# maclight-v1.net
KiCad netlist of a schematic drawn in EAGLE
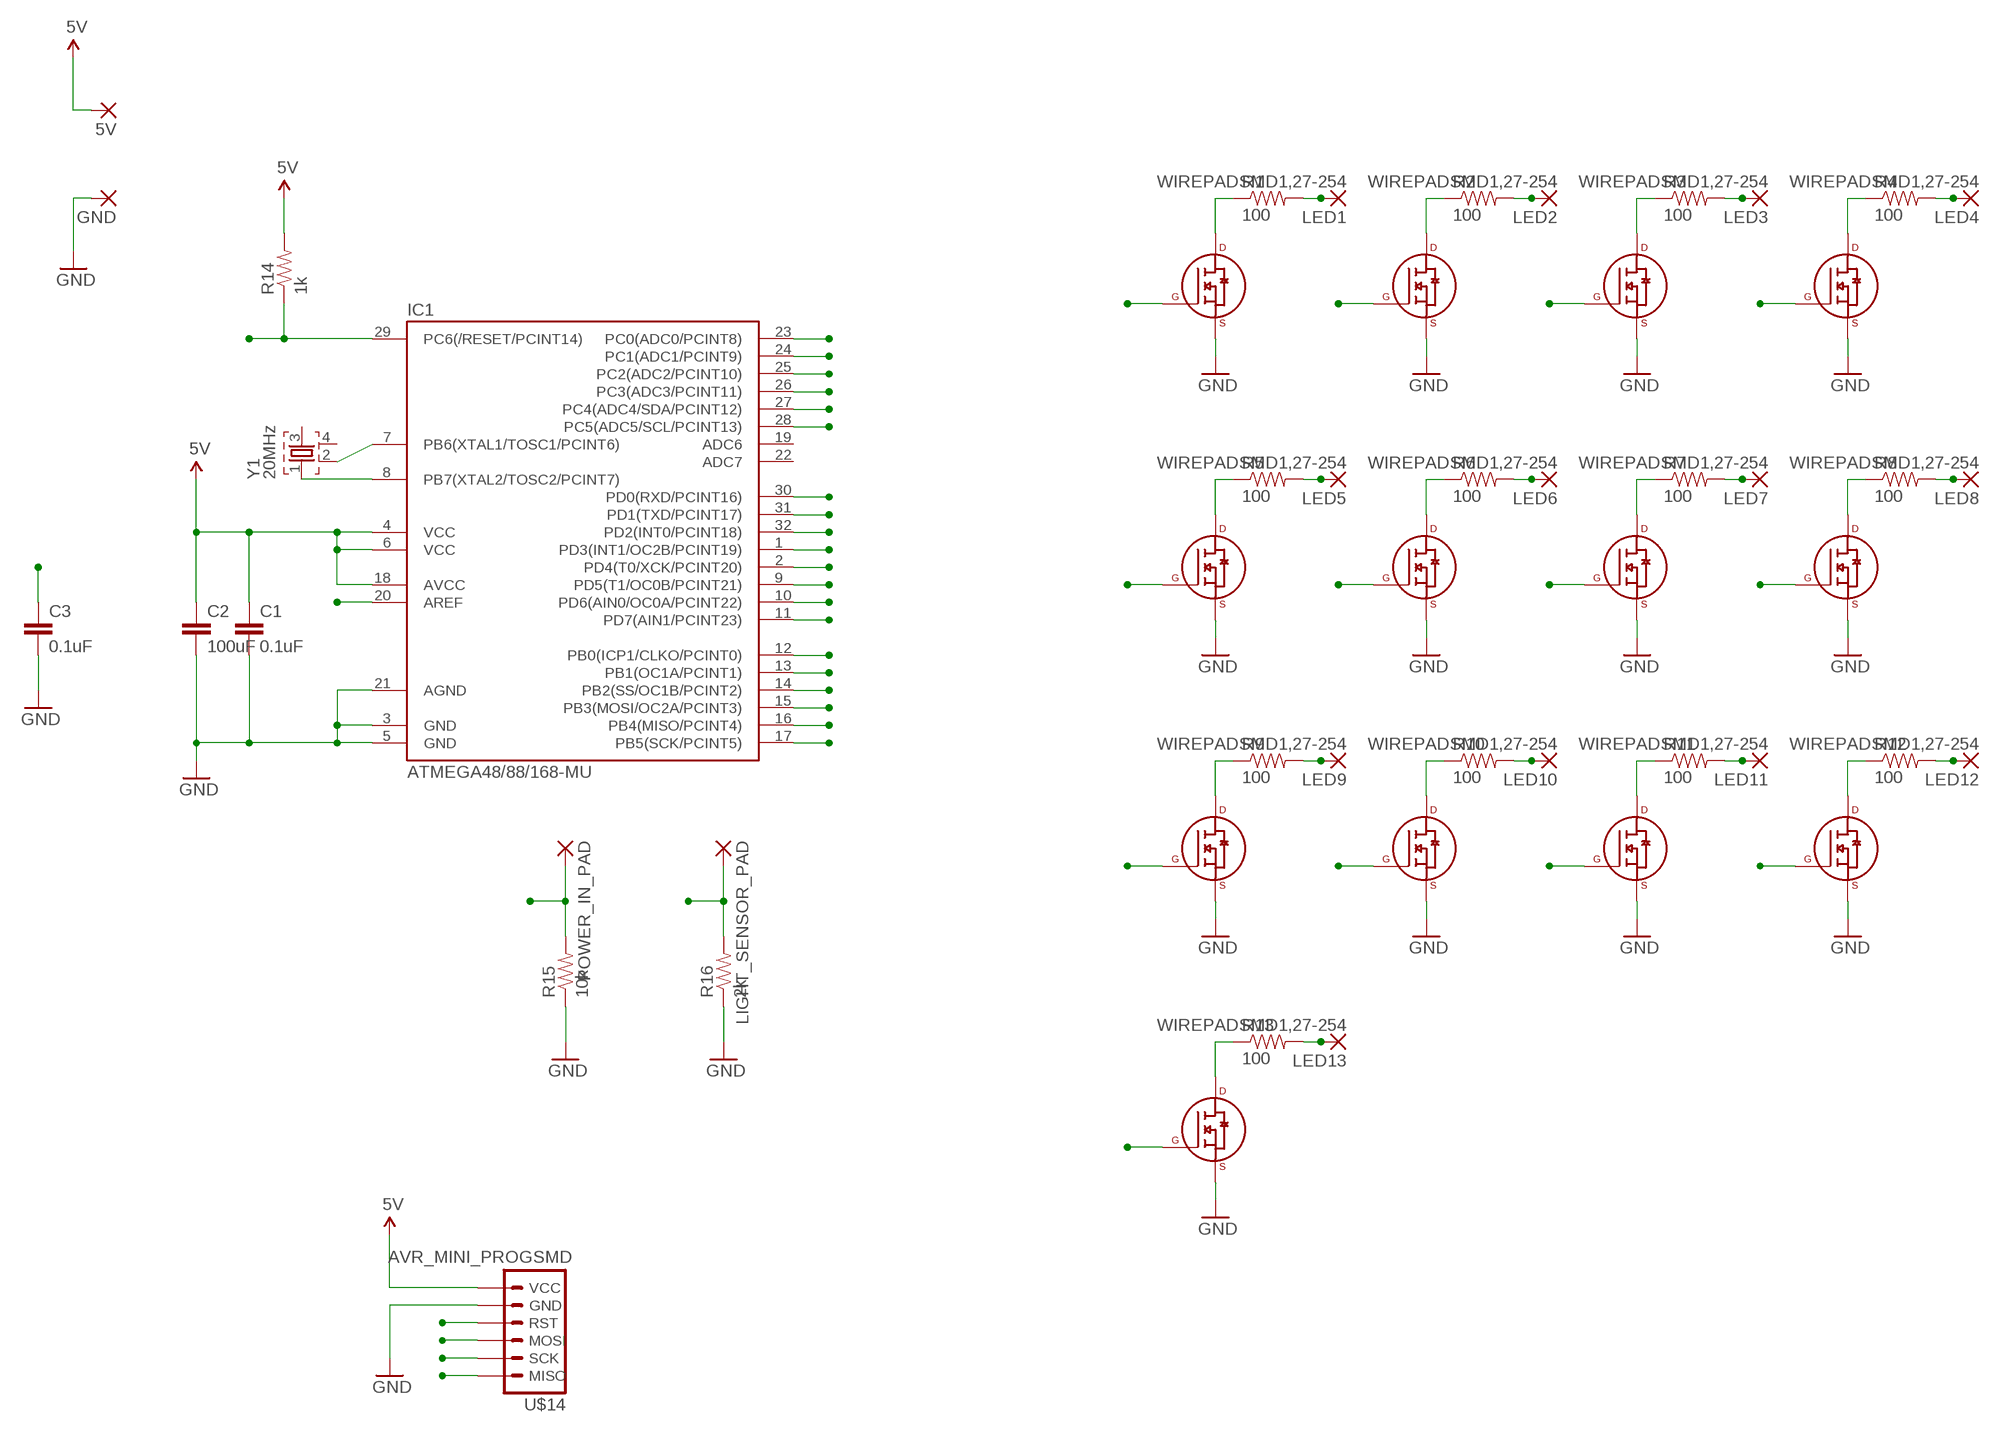
[diagram p0: schematic, sheet 1]

(export (version "E")
  (design (tool "Eeschema 10.0.6"))
  (components
    (comp (ref "5V")
      (value "WIREPADSMD5-1,8")
      (footprint "eagle-import:5-1,8")
      (libsource (lib "eagle-import") (part "WIREPADSMD5-1,8"))
    )
    (comp (ref "C1")
      (value "0.1uF")
      (footprint "eagle-import:0805")
      (libsource (lib "eagle-import") (part "CAP0805"))
    )
    (comp (ref "C2")
      (value "100uF")
      (footprint "eagle-import:1206")
      (libsource (lib "eagle-import") (part "CAP1206"))
    )
    (comp (ref "C3")
      (value "0.1uF")
      (footprint "eagle-import:0805")
      (libsource (lib "eagle-import") (part "CAP0805"))
    )
    (comp (ref "GND")
      (value "WIREPADSMD5-1,8")
      (footprint "eagle-import:5-1,8")
      (libsource (lib "eagle-import") (part "WIREPADSMD5-1,8"))
    )
    (comp (ref "IC1")
      (value "ATMEGA48/88/168-MU")
      (footprint "eagle-import:MLF32")
      (libsource (lib "eagle-import") (part "ATMEGA48/88/168-MU"))
    )
    (comp (ref "LED1")
      (value "WIREPADSMD1,27-254")
      (footprint "eagle-import:SMD1,27-2,54")
      (libsource (lib "eagle-import") (part "WIREPADSMD1,27-254"))
    )
    (comp (ref "LED2")
      (value "WIREPADSMD1,27-254")
      (footprint "eagle-import:SMD1,27-2,54")
      (libsource (lib "eagle-import") (part "WIREPADSMD1,27-254"))
    )
    (comp (ref "LED3")
      (value "WIREPADSMD1,27-254")
      (footprint "eagle-import:SMD1,27-2,54")
      (libsource (lib "eagle-import") (part "WIREPADSMD1,27-254"))
    )
    (comp (ref "LED4")
      (value "WIREPADSMD1,27-254")
      (footprint "eagle-import:SMD1,27-2,54")
      (libsource (lib "eagle-import") (part "WIREPADSMD1,27-254"))
    )
    (comp (ref "LED5")
      (value "WIREPADSMD1,27-254")
      (footprint "eagle-import:SMD1,27-2,54")
      (libsource (lib "eagle-import") (part "WIREPADSMD1,27-254"))
    )
    (comp (ref "LED6")
      (value "WIREPADSMD1,27-254")
      (footprint "eagle-import:SMD1,27-2,54")
      (libsource (lib "eagle-import") (part "WIREPADSMD1,27-254"))
    )
    (comp (ref "LED7")
      (value "WIREPADSMD1,27-254")
      (footprint "eagle-import:SMD1,27-2,54")
      (libsource (lib "eagle-import") (part "WIREPADSMD1,27-254"))
    )
    (comp (ref "LED8")
      (value "WIREPADSMD1,27-254")
      (footprint "eagle-import:SMD1,27-2,54")
      (libsource (lib "eagle-import") (part "WIREPADSMD1,27-254"))
    )
    (comp (ref "LED9")
      (value "WIREPADSMD1,27-254")
      (footprint "eagle-import:SMD1,27-2,54")
      (libsource (lib "eagle-import") (part "WIREPADSMD1,27-254"))
    )
    (comp (ref "LED10")
      (value "WIREPADSMD1,27-254")
      (footprint "eagle-import:SMD1,27-2,54")
      (libsource (lib "eagle-import") (part "WIREPADSMD1,27-254"))
    )
    (comp (ref "LED11")
      (value "WIREPADSMD1,27-254")
      (footprint "eagle-import:SMD1,27-2,54")
      (libsource (lib "eagle-import") (part "WIREPADSMD1,27-254"))
    )
    (comp (ref "LED12")
      (value "WIREPADSMD1,27-254")
      (footprint "eagle-import:SMD1,27-2,54")
      (libsource (lib "eagle-import") (part "WIREPADSMD1,27-254"))
    )
    (comp (ref "LED13")
      (value "WIREPADSMD1,27-254")
      (footprint "eagle-import:SMD1,27-2,54")
      (libsource (lib "eagle-import") (part "WIREPADSMD1,27-254"))
    )
    (comp (ref "LIGHT_SENSOR_PAD")
      (value "WIREPADSMD5-1,8")
      (footprint "eagle-import:5-1,8")
      (libsource (lib "eagle-import") (part "WIREPADSMD5-1,8"))
    )
    (comp (ref "POWER_IN_PAD")
      (value "WIREPADSMD5-1,8")
      (footprint "eagle-import:5-1,8")
      (libsource (lib "eagle-import") (part "WIREPADSMD5-1,8"))
    )
    (comp (ref "R1")
      (value "100")
      (footprint "eagle-import:0805")
      (libsource (lib "eagle-import") (part "RESISTOR0805-RES"))
    )
    (comp (ref "R2")
      (value "100")
      (footprint "eagle-import:0805")
      (libsource (lib "eagle-import") (part "RESISTOR0805-RES"))
    )
    (comp (ref "R3")
      (value "100")
      (footprint "eagle-import:0805")
      (libsource (lib "eagle-import") (part "RESISTOR0805-RES"))
    )
    (comp (ref "R4")
      (value "100")
      (footprint "eagle-import:0805")
      (libsource (lib "eagle-import") (part "RESISTOR0805-RES"))
    )
    (comp (ref "R5")
      (value "100")
      (footprint "eagle-import:0805")
      (libsource (lib "eagle-import") (part "RESISTOR0805-RES"))
    )
    (comp (ref "R6")
      (value "100")
      (footprint "eagle-import:0805")
      (libsource (lib "eagle-import") (part "RESISTOR0805-RES"))
    )
    (comp (ref "R7")
      (value "100")
      (footprint "eagle-import:0805")
      (libsource (lib "eagle-import") (part "RESISTOR0805-RES"))
    )
    (comp (ref "R8")
      (value "100")
      (footprint "eagle-import:0805")
      (libsource (lib "eagle-import") (part "RESISTOR0805-RES"))
    )
    (comp (ref "R9")
      (value "100")
      (footprint "eagle-import:0805")
      (libsource (lib "eagle-import") (part "RESISTOR0805-RES"))
    )
    (comp (ref "R10")
      (value "100")
      (footprint "eagle-import:0805")
      (libsource (lib "eagle-import") (part "RESISTOR0805-RES"))
    )
    (comp (ref "R11")
      (value "100")
      (footprint "eagle-import:0805")
      (libsource (lib "eagle-import") (part "RESISTOR0805-RES"))
    )
    (comp (ref "R12")
      (value "100")
      (footprint "eagle-import:0805")
      (libsource (lib "eagle-import") (part "RESISTOR0805-RES"))
    )
    (comp (ref "R13")
      (value "100")
      (footprint "eagle-import:0805")
      (libsource (lib "eagle-import") (part "RESISTOR0805-RES"))
    )
    (comp (ref "R14")
      (value "1k")
      (footprint "eagle-import:0805")
      (libsource (lib "eagle-import") (part "RESISTOR0805-RES"))
    )
    (comp (ref "R15")
      (value "10k")
      (footprint "eagle-import:0805")
      (libsource (lib "eagle-import") (part "RESISTOR0805-RES"))
    )
    (comp (ref "R16")
      (value "2k")
      (footprint "eagle-import:0805")
      (libsource (lib "eagle-import") (part "RESISTOR0805-RES"))
    )
    (comp (ref "U$1")
      (value "2N7000-2SOT-23")
      (footprint "eagle-import:SOT-23-3")
      (libsource (lib "eagle-import") (part "2N7000-2SOT-23"))
    )
    (comp (ref "U$2")
      (value "2N7000-2SOT-23")
      (footprint "eagle-import:SOT-23-3")
      (libsource (lib "eagle-import") (part "2N7000-2SOT-23"))
    )
    (comp (ref "U$3")
      (value "2N7000-2SOT-23")
      (footprint "eagle-import:SOT-23-3")
      (libsource (lib "eagle-import") (part "2N7000-2SOT-23"))
    )
    (comp (ref "U$4")
      (value "2N7000-2SOT-23")
      (footprint "eagle-import:SOT-23-3")
      (libsource (lib "eagle-import") (part "2N7000-2SOT-23"))
    )
    (comp (ref "U$5")
      (value "2N7000-2SOT-23")
      (footprint "eagle-import:SOT-23-3")
      (libsource (lib "eagle-import") (part "2N7000-2SOT-23"))
    )
    (comp (ref "U$6")
      (value "2N7000-2SOT-23")
      (footprint "eagle-import:SOT-23-3")
      (libsource (lib "eagle-import") (part "2N7000-2SOT-23"))
    )
    (comp (ref "U$7")
      (value "2N7000-2SOT-23")
      (footprint "eagle-import:SOT-23-3")
      (libsource (lib "eagle-import") (part "2N7000-2SOT-23"))
    )
    (comp (ref "U$8")
      (value "2N7000-2SOT-23")
      (footprint "eagle-import:SOT-23-3")
      (libsource (lib "eagle-import") (part "2N7000-2SOT-23"))
    )
    (comp (ref "U$9")
      (value "2N7000-2SOT-23")
      (footprint "eagle-import:SOT-23-3")
      (libsource (lib "eagle-import") (part "2N7000-2SOT-23"))
    )
    (comp (ref "U$10")
      (value "2N7000-2SOT-23")
      (footprint "eagle-import:SOT-23-3")
      (libsource (lib "eagle-import") (part "2N7000-2SOT-23"))
    )
    (comp (ref "U$11")
      (value "2N7000-2SOT-23")
      (footprint "eagle-import:SOT-23-3")
      (libsource (lib "eagle-import") (part "2N7000-2SOT-23"))
    )
    (comp (ref "U$12")
      (value "2N7000-2SOT-23")
      (footprint "eagle-import:SOT-23-3")
      (libsource (lib "eagle-import") (part "2N7000-2SOT-23"))
    )
    (comp (ref "U$13")
      (value "2N7000-2SOT-23")
      (footprint "eagle-import:SOT-23-3")
      (libsource (lib "eagle-import") (part "2N7000-2SOT-23"))
    )
    (comp (ref "U$14")
      (value "AVR_MINI_PROGSMD")
      (footprint "eagle-import:AVR_MINI_PROG")
      (libsource (lib "eagle-import") (part "AVR_MINI_PROGSMD"))
    )
    (comp (ref "Y1")
      (value "20MHz")
      (footprint "eagle-import:FA-20H")
      (libsource (lib "eagle-import") (part "FA-20H"))
    )
  )
  (nets
    (net (code "1") (name "/AREF") (class "Default")
      (node (ref "C3") (pin "1") (pinfunction "1_1") (pintype "passive"))
      (node (ref "IC1") (pin "20") (pinfunction "AREF_20") (pintype "passive"))
    )
    (net (code "2") (name "/LED1") (class "Default")
      (node (ref "IC1") (pin "30") (pinfunction "PD0(RXD/PCINT16)_30") (pintype "bidirectional"))
      (node (ref "U$1") (pin "1") (pinfunction "G_1") (pintype "bidirectional"))
    )
    (net (code "3") (name "/LED2") (class "Default")
      (node (ref "IC1") (pin "31") (pinfunction "PD1(TXD/PCINT17)_31") (pintype "bidirectional"))
      (node (ref "U$2") (pin "1") (pinfunction "G_1") (pintype "bidirectional"))
    )
    (net (code "4") (name "/LED3") (class "Default")
      (node (ref "IC1") (pin "32") (pinfunction "PD2(INT0/PCINT18)_32") (pintype "bidirectional"))
      (node (ref "U$3") (pin "1") (pinfunction "G_1") (pintype "bidirectional"))
    )
    (net (code "5") (name "/LED4") (class "Default")
      (node (ref "IC1") (pin "1") (pinfunction "PD3(INT1/OC2B/PCINT19)_1") (pintype "bidirectional"))
      (node (ref "U$4") (pin "1") (pinfunction "G_1") (pintype "bidirectional"))
    )
    (net (code "6") (name "/LED5") (class "Default")
      (node (ref "IC1") (pin "2") (pinfunction "PD4(T0/XCK/PCINT20)_2") (pintype "bidirectional"))
      (node (ref "U$5") (pin "1") (pinfunction "G_1") (pintype "bidirectional"))
    )
    (net (code "7") (name "/LED6") (class "Default")
      (node (ref "IC1") (pin "9") (pinfunction "PD5(T1/OC0B/PCINT21)_9") (pintype "bidirectional"))
      (node (ref "U$6") (pin "1") (pinfunction "G_1") (pintype "bidirectional"))
    )
    (net (code "8") (name "/LED7") (class "Default")
      (node (ref "IC1") (pin "10") (pinfunction "PD6(AIN0/OC0A/PCINT22)_10") (pintype "bidirectional"))
      (node (ref "U$7") (pin "1") (pinfunction "G_1") (pintype "bidirectional"))
    )
    (net (code "9") (name "/LED8") (class "Default")
      (node (ref "IC1") (pin "11") (pinfunction "PD7(AIN1/PCINT23)_11") (pintype "bidirectional"))
      (node (ref "U$8") (pin "1") (pinfunction "G_1") (pintype "bidirectional"))
    )
    (net (code "10") (name "/LED9") (class "Default")
      (node (ref "IC1") (pin "12") (pinfunction "PB0(ICP1/CLKO/PCINT0)_12") (pintype "bidirectional"))
      (node (ref "U$9") (pin "1") (pinfunction "G_1") (pintype "bidirectional"))
    )
    (net (code "11") (name "/LED10") (class "Default")
      (node (ref "IC1") (pin "13") (pinfunction "PB1(OC1A/PCINT1)_13") (pintype "bidirectional"))
      (node (ref "U$10") (pin "1") (pinfunction "G_1") (pintype "bidirectional"))
    )
    (net (code "12") (name "/LED11") (class "Default")
      (node (ref "IC1") (pin "14") (pinfunction "PB2(SS/OC1B/PCINT2)_14") (pintype "bidirectional"))
      (node (ref "U$11") (pin "1") (pinfunction "G_1") (pintype "bidirectional"))
    )
    (net (code "13") (name "/LIGHT_SENSOR") (class "Default")
      (node (ref "IC1") (pin "24") (pinfunction "PC1(ADC1/PCINT9)_24") (pintype "bidirectional"))
      (node (ref "LIGHT_SENSOR_PAD") (pin "1") (pinfunction "P_1") (pintype "passive"))
      (node (ref "R16") (pin "2") (pinfunction "2_2") (pintype "passive"))
    )
    (net (code "14") (name "/MISO") (class "Default")
      (node (ref "IC1") (pin "16") (pinfunction "PB4(MISO/PCINT4)_16") (pintype "bidirectional"))
      (node (ref "U$13") (pin "1") (pinfunction "G_1") (pintype "bidirectional"))
      (node (ref "U$14") (pin "6") (pinfunction "MISO_6") (pintype "passive"))
    )
    (net (code "15") (name "/MOSI") (class "Default")
      (node (ref "IC1") (pin "15") (pinfunction "PB3(MOSI/OC2A/PCINT3)_15") (pintype "bidirectional"))
      (node (ref "U$12") (pin "1") (pinfunction "G_1") (pintype "bidirectional"))
      (node (ref "U$14") (pin "4") (pinfunction "MOSI_4") (pintype "passive"))
    )
    (net (code "16") (name "/POWER_IN") (class "Default")
      (node (ref "IC1") (pin "23") (pinfunction "PC0(ADC0/PCINT8)_23") (pintype "bidirectional"))
      (node (ref "POWER_IN_PAD") (pin "1") (pinfunction "P_1") (pintype "passive"))
      (node (ref "R15") (pin "2") (pinfunction "2_2") (pintype "passive"))
    )
    (net (code "17") (name "/SCK") (class "Default")
      (node (ref "IC1") (pin "17") (pinfunction "PB5(SCK/PCINT5)_17") (pintype "bidirectional"))
      (node (ref "U$14") (pin "5") (pinfunction "SCK_5") (pintype "passive"))
    )
    (net (code "18") (name "/{slash}RESET") (class "Default")
      (node (ref "IC1") (pin "29") (pinfunction "PC6(/RESET/PCINT14)_29") (pintype "bidirectional"))
      (node (ref "R14") (pin "1") (pinfunction "1_1") (pintype "passive"))
      (node (ref "U$14") (pin "3") (pinfunction "RST_3") (pintype "passive"))
    )
    (net (code "19") (name "5V") (class "Default")
      (node (ref "5V") (pin "1") (pinfunction "P_1") (pintype "passive"))
      (node (ref "C1") (pin "1") (pinfunction "1_1") (pintype "passive"))
      (node (ref "C2") (pin "1") (pinfunction "1_1") (pintype "passive"))
      (node (ref "IC1") (pin "18") (pinfunction "AVCC_18") (pintype "passive"))
      (node (ref "IC1") (pin "4") (pinfunction "VCC_4") (pintype "power_in"))
      (node (ref "IC1") (pin "6") (pinfunction "VCC_6") (pintype "power_in"))
      (node (ref "R14") (pin "2") (pinfunction "2_2") (pintype "passive"))
      (node (ref "U$14") (pin "1") (pinfunction "VCC_1") (pintype "passive"))
    )
    (net (code "20") (name "GND") (class "Default")
      (node (ref "C1") (pin "2") (pinfunction "2_2") (pintype "passive"))
      (node (ref "C2") (pin "2") (pinfunction "2_2") (pintype "passive"))
      (node (ref "C3") (pin "2") (pinfunction "2_2") (pintype "passive"))
      (node (ref "GND") (pin "1") (pinfunction "P_1") (pintype "passive"))
      (node (ref "IC1") (pin "21") (pinfunction "AGND_21") (pintype "power_in"))
      (node (ref "IC1") (pin "3") (pinfunction "GND_3") (pintype "power_in"))
      (node (ref "IC1") (pin "5") (pinfunction "GND_5") (pintype "power_in"))
      (node (ref "R15") (pin "1") (pinfunction "1_1") (pintype "passive"))
      (node (ref "R16") (pin "1") (pinfunction "1_1") (pintype "passive"))
      (node (ref "U$1") (pin "2") (pinfunction "S_2") (pintype "bidirectional"))
      (node (ref "U$10") (pin "2") (pinfunction "S_2") (pintype "bidirectional"))
      (node (ref "U$11") (pin "2") (pinfunction "S_2") (pintype "bidirectional"))
      (node (ref "U$12") (pin "2") (pinfunction "S_2") (pintype "bidirectional"))
      (node (ref "U$13") (pin "2") (pinfunction "S_2") (pintype "bidirectional"))
      (node (ref "U$14") (pin "2") (pinfunction "GND_2") (pintype "passive"))
      (node (ref "U$2") (pin "2") (pinfunction "S_2") (pintype "bidirectional"))
      (node (ref "U$3") (pin "2") (pinfunction "S_2") (pintype "bidirectional"))
      (node (ref "U$4") (pin "2") (pinfunction "S_2") (pintype "bidirectional"))
      (node (ref "U$5") (pin "2") (pinfunction "S_2") (pintype "bidirectional"))
      (node (ref "U$6") (pin "2") (pinfunction "S_2") (pintype "bidirectional"))
      (node (ref "U$7") (pin "2") (pinfunction "S_2") (pintype "bidirectional"))
      (node (ref "U$8") (pin "2") (pinfunction "S_2") (pintype "bidirectional"))
      (node (ref "U$9") (pin "2") (pinfunction "S_2") (pintype "bidirectional"))
    )
    (net (code "21") (name "Net-(IC1-PB6(XTAL1{slash}TOSC1{slash}PCINT6))") (class "Default")
      (node (ref "IC1") (pin "7") (pinfunction "PB6(XTAL1/TOSC1/PCINT6)_7") (pintype "bidirectional"))
      (node (ref "Y1") (pin "2") (pinfunction "2_2") (pintype "passive"))
    )
    (net (code "22") (name "Net-(IC1-PB7(XTAL2{slash}TOSC2{slash}PCINT7))") (class "Default")
      (node (ref "IC1") (pin "8") (pinfunction "PB7(XTAL2/TOSC2/PCINT7)_8") (pintype "bidirectional"))
      (node (ref "Y1") (pin "1") (pinfunction "1_1") (pintype "passive"))
    )
    (net (code "23") (name "Net-(LED1-P)") (class "Default")
      (node (ref "LED1") (pin "1") (pinfunction "P_1") (pintype "passive"))
      (node (ref "R1") (pin "2") (pinfunction "2_2") (pintype "passive"))
    )
    (net (code "24") (name "Net-(LED2-P)") (class "Default")
      (node (ref "LED2") (pin "1") (pinfunction "P_1") (pintype "passive"))
      (node (ref "R2") (pin "2") (pinfunction "2_2") (pintype "passive"))
    )
    (net (code "25") (name "Net-(LED3-P)") (class "Default")
      (node (ref "LED3") (pin "1") (pinfunction "P_1") (pintype "passive"))
      (node (ref "R3") (pin "2") (pinfunction "2_2") (pintype "passive"))
    )
    (net (code "26") (name "Net-(LED4-P)") (class "Default")
      (node (ref "LED4") (pin "1") (pinfunction "P_1") (pintype "passive"))
      (node (ref "R4") (pin "2") (pinfunction "2_2") (pintype "passive"))
    )
    (net (code "27") (name "Net-(LED5-P)") (class "Default")
      (node (ref "LED5") (pin "1") (pinfunction "P_1") (pintype "passive"))
      (node (ref "R5") (pin "2") (pinfunction "2_2") (pintype "passive"))
    )
    (net (code "28") (name "Net-(LED6-P)") (class "Default")
      (node (ref "LED6") (pin "1") (pinfunction "P_1") (pintype "passive"))
      (node (ref "R6") (pin "2") (pinfunction "2_2") (pintype "passive"))
    )
    (net (code "29") (name "Net-(LED7-P)") (class "Default")
      (node (ref "LED7") (pin "1") (pinfunction "P_1") (pintype "passive"))
      (node (ref "R7") (pin "2") (pinfunction "2_2") (pintype "passive"))
    )
    (net (code "30") (name "Net-(LED8-P)") (class "Default")
      (node (ref "LED8") (pin "1") (pinfunction "P_1") (pintype "passive"))
      (node (ref "R8") (pin "2") (pinfunction "2_2") (pintype "passive"))
    )
    (net (code "31") (name "Net-(LED9-P)") (class "Default")
      (node (ref "LED9") (pin "1") (pinfunction "P_1") (pintype "passive"))
      (node (ref "R9") (pin "2") (pinfunction "2_2") (pintype "passive"))
    )
    (net (code "32") (name "Net-(LED10-P)") (class "Default")
      (node (ref "LED10") (pin "1") (pinfunction "P_1") (pintype "passive"))
      (node (ref "R10") (pin "2") (pinfunction "2_2") (pintype "passive"))
    )
    (net (code "33") (name "Net-(LED11-P)") (class "Default")
      (node (ref "LED11") (pin "1") (pinfunction "P_1") (pintype "passive"))
      (node (ref "R11") (pin "2") (pinfunction "2_2") (pintype "passive"))
    )
    (net (code "34") (name "Net-(LED12-P)") (class "Default")
      (node (ref "LED12") (pin "1") (pinfunction "P_1") (pintype "passive"))
      (node (ref "R12") (pin "2") (pinfunction "2_2") (pintype "passive"))
    )
    (net (code "35") (name "Net-(LED13-P)") (class "Default")
      (node (ref "LED13") (pin "1") (pinfunction "P_1") (pintype "passive"))
      (node (ref "R13") (pin "2") (pinfunction "2_2") (pintype "passive"))
    )
    (net (code "36") (name "Net-(U$1-D)") (class "Default")
      (node (ref "R1") (pin "1") (pinfunction "1_1") (pintype "passive"))
      (node (ref "U$1") (pin "3") (pinfunction "D_3") (pintype "bidirectional"))
    )
    (net (code "37") (name "Net-(U$2-D)") (class "Default")
      (node (ref "R2") (pin "1") (pinfunction "1_1") (pintype "passive"))
      (node (ref "U$2") (pin "3") (pinfunction "D_3") (pintype "bidirectional"))
    )
    (net (code "38") (name "Net-(U$3-D)") (class "Default")
      (node (ref "R3") (pin "1") (pinfunction "1_1") (pintype "passive"))
      (node (ref "U$3") (pin "3") (pinfunction "D_3") (pintype "bidirectional"))
    )
    (net (code "39") (name "Net-(U$4-D)") (class "Default")
      (node (ref "R4") (pin "1") (pinfunction "1_1") (pintype "passive"))
      (node (ref "U$4") (pin "3") (pinfunction "D_3") (pintype "bidirectional"))
    )
    (net (code "40") (name "Net-(U$5-D)") (class "Default")
      (node (ref "R5") (pin "1") (pinfunction "1_1") (pintype "passive"))
      (node (ref "U$5") (pin "3") (pinfunction "D_3") (pintype "bidirectional"))
    )
    (net (code "41") (name "Net-(U$6-D)") (class "Default")
      (node (ref "R6") (pin "1") (pinfunction "1_1") (pintype "passive"))
      (node (ref "U$6") (pin "3") (pinfunction "D_3") (pintype "bidirectional"))
    )
    (net (code "42") (name "Net-(U$7-D)") (class "Default")
      (node (ref "R7") (pin "1") (pinfunction "1_1") (pintype "passive"))
      (node (ref "U$7") (pin "3") (pinfunction "D_3") (pintype "bidirectional"))
    )
    (net (code "43") (name "Net-(U$8-D)") (class "Default")
      (node (ref "R8") (pin "1") (pinfunction "1_1") (pintype "passive"))
      (node (ref "U$8") (pin "3") (pinfunction "D_3") (pintype "bidirectional"))
    )
    (net (code "44") (name "Net-(U$9-D)") (class "Default")
      (node (ref "R9") (pin "1") (pinfunction "1_1") (pintype "passive"))
      (node (ref "U$9") (pin "3") (pinfunction "D_3") (pintype "bidirectional"))
    )
    (net (code "45") (name "Net-(U$10-D)") (class "Default")
      (node (ref "R10") (pin "1") (pinfunction "1_1") (pintype "passive"))
      (node (ref "U$10") (pin "3") (pinfunction "D_3") (pintype "bidirectional"))
    )
    (net (code "46") (name "Net-(U$11-D)") (class "Default")
      (node (ref "R11") (pin "1") (pinfunction "1_1") (pintype "passive"))
      (node (ref "U$11") (pin "3") (pinfunction "D_3") (pintype "bidirectional"))
    )
    (net (code "47") (name "Net-(U$12-D)") (class "Default")
      (node (ref "R12") (pin "1") (pinfunction "1_1") (pintype "passive"))
      (node (ref "U$12") (pin "3") (pinfunction "D_3") (pintype "bidirectional"))
    )
    (net (code "48") (name "Net-(U$13-D)") (class "Default")
      (node (ref "R13") (pin "1") (pinfunction "1_1") (pintype "passive"))
      (node (ref "U$13") (pin "3") (pinfunction "D_3") (pintype "bidirectional"))
    )
    (net (code "49") (name "unconnected-(IC1-ADC6-Pad19)") (class "Default")
      (node (ref "IC1") (pin "19") (pinfunction "ADC6_19") (pintype "passive"))
    )
    (net (code "50") (name "unconnected-(IC1-ADC7-Pad22)") (class "Default")
      (node (ref "IC1") (pin "22") (pinfunction "ADC7_22") (pintype "passive"))
    )
    (net (code "51") (name "unconnected-(IC1-PC2(ADC2{slash}PCINT10)-Pad25)") (class "Default")
      (node (ref "IC1") (pin "25") (pinfunction "PC2(ADC2/PCINT10)_25") (pintype "bidirectional"))
    )
    (net (code "52") (name "unconnected-(IC1-PC3(ADC3{slash}PCINT11)-Pad26)") (class "Default")
      (node (ref "IC1") (pin "26") (pinfunction "PC3(ADC3/PCINT11)_26") (pintype "bidirectional"))
    )
    (net (code "53") (name "unconnected-(IC1-PC4(ADC4{slash}SDA{slash}PCINT12)-Pad27)") (class "Default")
      (node (ref "IC1") (pin "27") (pinfunction "PC4(ADC4/SDA/PCINT12)_27") (pintype "bidirectional"))
    )
    (net (code "54") (name "unconnected-(IC1-PC5(ADC5{slash}SCL{slash}PCINT13)-Pad28)") (class "Default")
      (node (ref "IC1") (pin "28") (pinfunction "PC5(ADC5/SCL/PCINT13)_28") (pintype "bidirectional"))
    )
    (net (code "55") (name "unconnected-(Y1-Pad3)") (class "Default")
      (node (ref "Y1") (pin "3") (pinfunction "3_3") (pintype "passive"))
    )
    (net (code "56") (name "unconnected-(Y1-Pad4)") (class "Default")
      (node (ref "Y1") (pin "4") (pinfunction "4_4") (pintype "passive"))
    )
  )
)
